# CncBooster_1_1.net
KiCad netlist of a schematic drawn in EAGLE
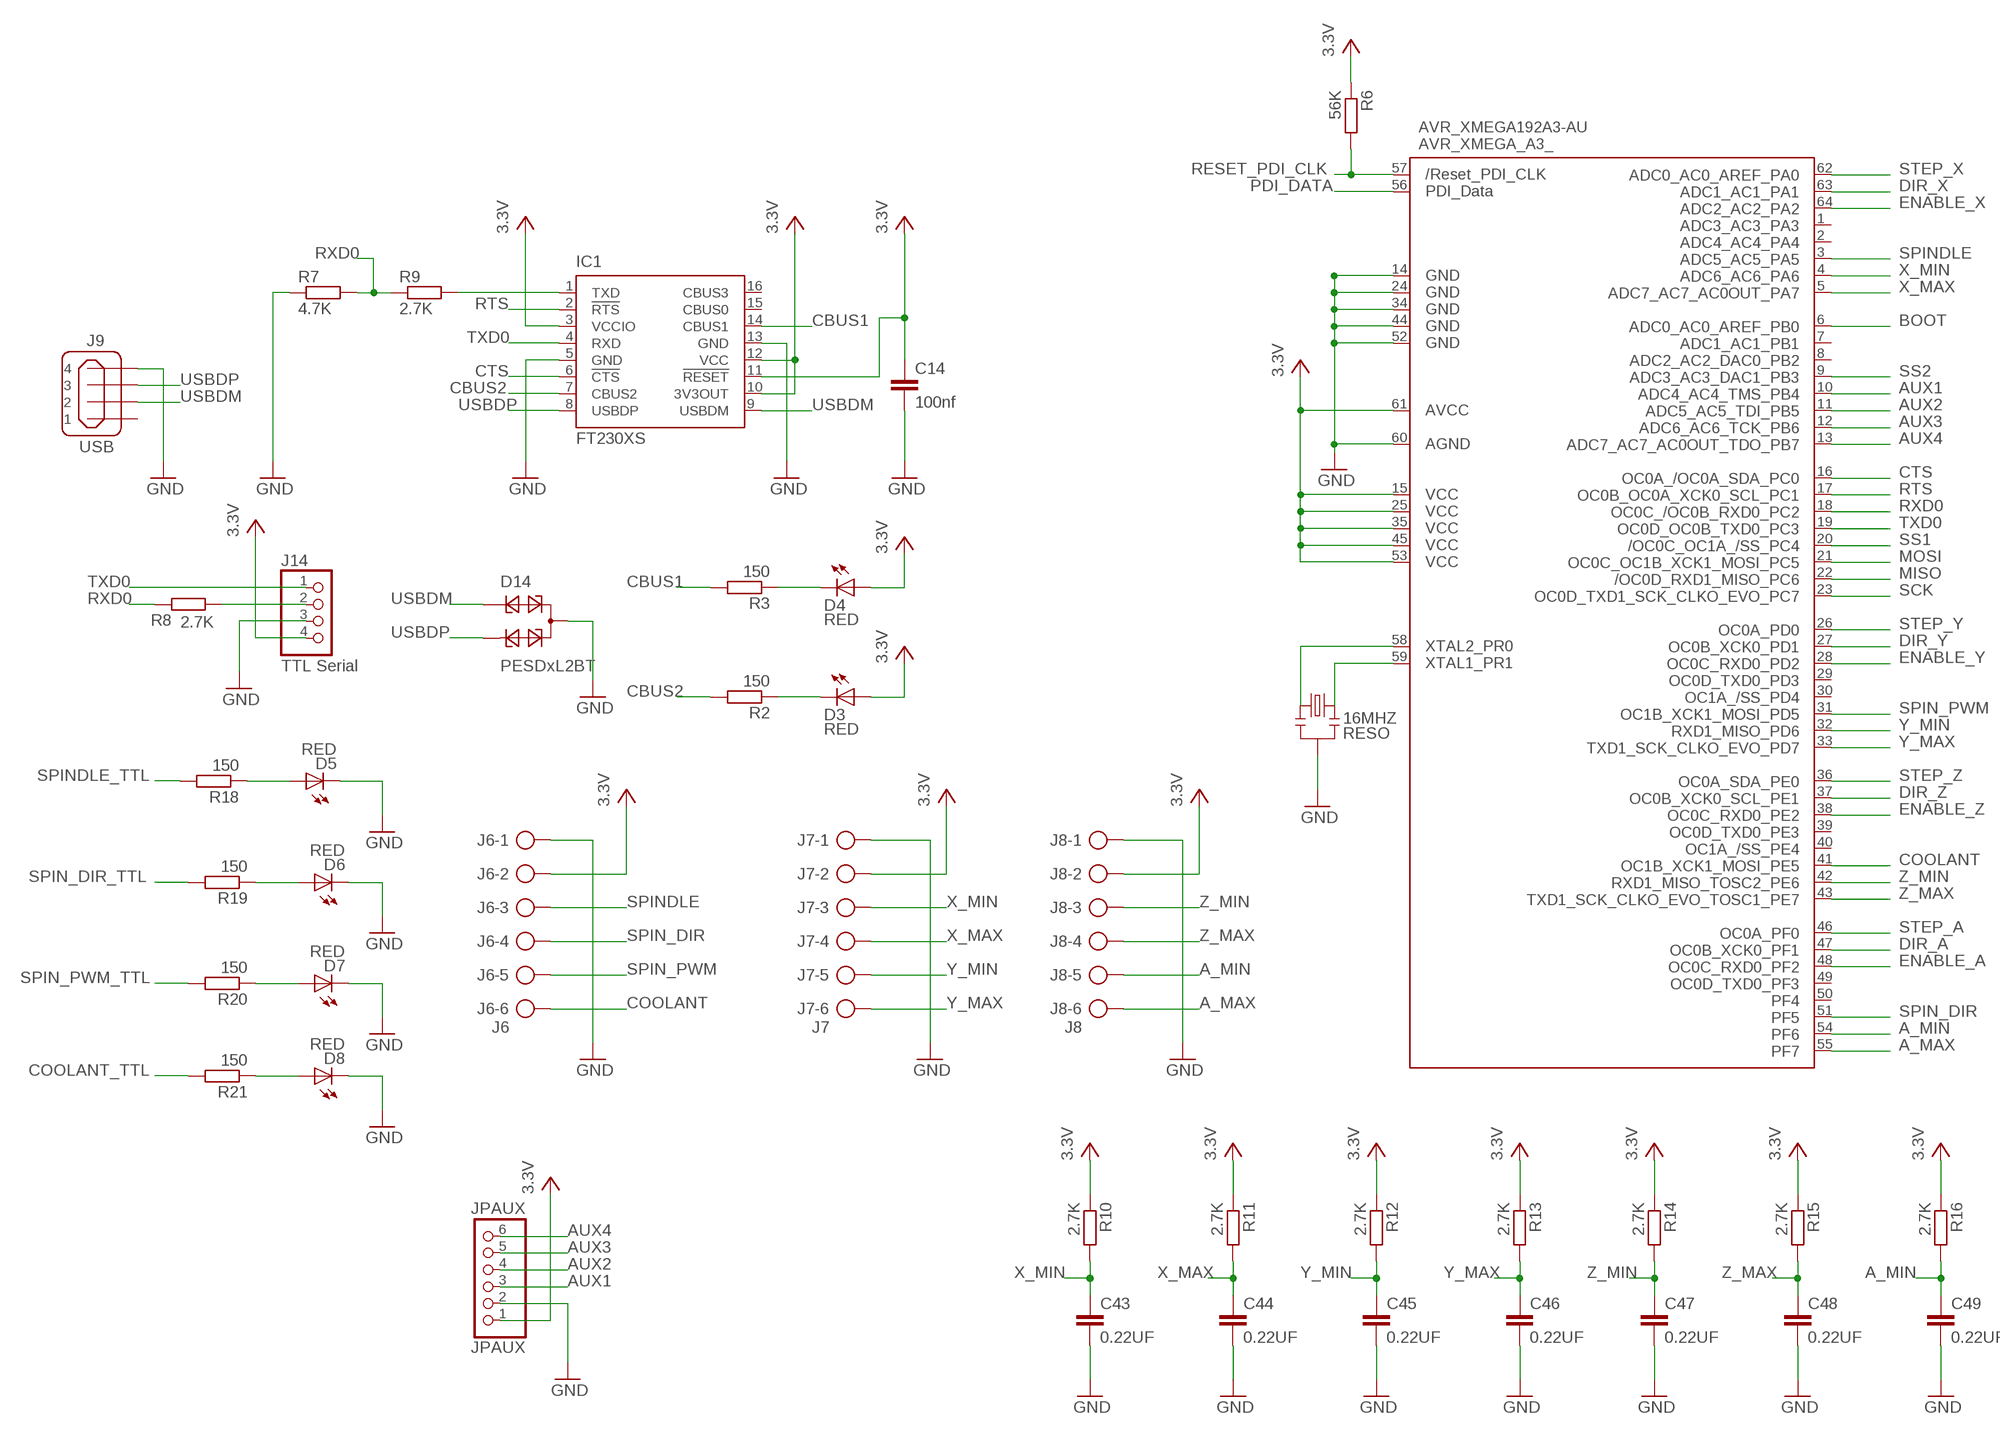
[diagram p0: schematic, sheet 1, part 1 of 2]
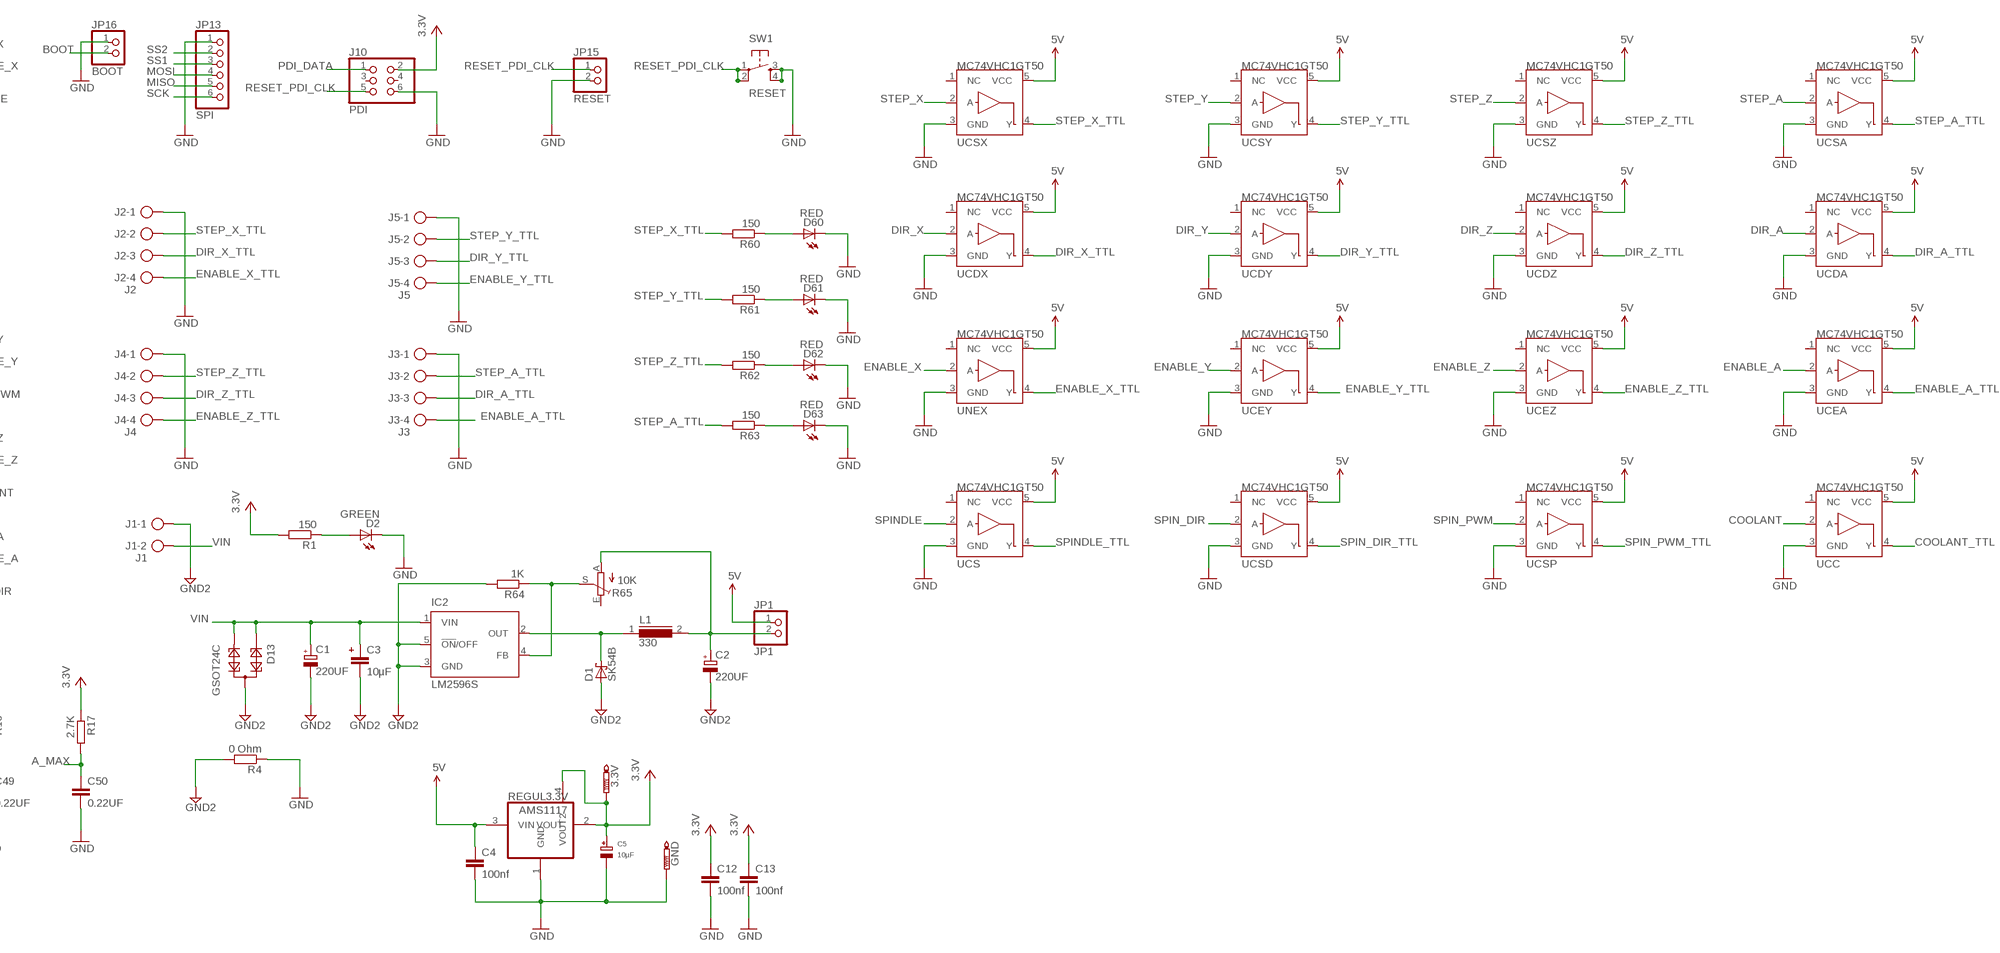
[diagram p1: schematic, sheet 1, part 2 of 2]

(export (version "E")
  (design (tool "Eeschema 10.0.6"))
  (components
    (comp (ref "3.3V")
      (value "PTR1B1,27")
      (footprint "eagle-import:B1,27")
      (libsource (lib "eagle-import") (part "PTR1B1,27"))
    )
    (comp (ref "16MHZ")
      (value "RESO")
      (footprint "eagle-import:RESONATOR_CMS_AWSCR")
      (libsource (lib "eagle-import") (part "RESONATOR_CMS"))
    )
    (comp (ref "AVR_XMEGA192A3-AU")
      (value "AVR_XMEGA_A3_")
      (footprint "eagle-import:TQFP64")
      (libsource (lib "eagle-import") (part "AVR_XMEGA_A3_"))
    )
    (comp (ref "C1")
      (value "220UF")
      (footprint "eagle-import:PANASONIC_E")
      (libsource (lib "eagle-import") (part "CPOL-EUE"))
    )
    (comp (ref "C2")
      (value "220UF")
      (footprint "eagle-import:PANASONIC_E")
      (libsource (lib "eagle-import") (part "CPOL-EUE"))
    )
    (comp (ref "C3")
      (value "10µF")
      (footprint "eagle-import:CONDO_1206")
      (libsource (lib "eagle-import") (part "CONDO_1206_POLA"))
    )
    (comp (ref "C4")
      (value "100nf")
      (footprint "eagle-import:C1206")
      (libsource (lib "eagle-import") (part "C-EUC1206"))
    )
    (comp (ref "C5")
      (value "10µF")
      (footprint "eagle-import:EIA3216-18_A-W")
      (libsource (lib "eagle-import") (part "CAP_TANTALUMA/3216_WAVE"))
    )
    (comp (ref "C12")
      (value "100nf")
      (footprint "eagle-import:C1206")
      (libsource (lib "eagle-import") (part "C-EUC1206"))
    )
    (comp (ref "C13")
      (value "100nf")
      (footprint "eagle-import:C1206")
      (libsource (lib "eagle-import") (part "C-EUC1206"))
    )
    (comp (ref "C14")
      (value "100nf")
      (footprint "eagle-import:C1206")
      (libsource (lib "eagle-import") (part "C-EUC1206"))
    )
    (comp (ref "C43")
      (value "0.22UF")
      (footprint "eagle-import:C1206")
      (libsource (lib "eagle-import") (part "C-EUC1206"))
    )
    (comp (ref "C44")
      (value "0.22UF")
      (footprint "eagle-import:C1206")
      (libsource (lib "eagle-import") (part "C-EUC1206"))
    )
    (comp (ref "C45")
      (value "0.22UF")
      (footprint "eagle-import:C1206")
      (libsource (lib "eagle-import") (part "C-EUC1206"))
    )
    (comp (ref "C46")
      (value "0.22UF")
      (footprint "eagle-import:C1206")
      (libsource (lib "eagle-import") (part "C-EUC1206"))
    )
    (comp (ref "C47")
      (value "0.22UF")
      (footprint "eagle-import:C1206")
      (libsource (lib "eagle-import") (part "C-EUC1206"))
    )
    (comp (ref "C48")
      (value "0.22UF")
      (footprint "eagle-import:C1206")
      (libsource (lib "eagle-import") (part "C-EUC1206"))
    )
    (comp (ref "C49")
      (value "0.22UF")
      (footprint "eagle-import:C1206")
      (libsource (lib "eagle-import") (part "C-EUC1206"))
    )
    (comp (ref "C50")
      (value "0.22UF")
      (footprint "eagle-import:C1206")
      (libsource (lib "eagle-import") (part "C-EUC1206"))
    )
    (comp (ref "D1")
      (value "SK54B")
      (footprint "eagle-import:DO-214AA")
      (libsource (lib "eagle-import") (part "SK54B"))
    )
    (comp (ref "D2")
      (value "GREEN")
      (footprint "eagle-import:CHIPLED_1206")
      (libsource (lib "eagle-import") (part "LEDCHIPLED_1206"))
    )
    (comp (ref "D3")
      (value "RED")
      (footprint "eagle-import:CHIPLED_1206")
      (libsource (lib "eagle-import") (part "LEDCHIPLED_1206"))
    )
    (comp (ref "D4")
      (value "RED")
      (footprint "eagle-import:CHIPLED_1206")
      (libsource (lib "eagle-import") (part "LEDCHIPLED_1206"))
    )
    (comp (ref "D5")
      (value "RED")
      (footprint "eagle-import:CHIPLED_1206")
      (libsource (lib "eagle-import") (part "LEDCHIPLED_1206"))
    )
    (comp (ref "D6")
      (value "RED")
      (footprint "eagle-import:CHIPLED_1206")
      (libsource (lib "eagle-import") (part "LEDCHIPLED_1206"))
    )
    (comp (ref "D7")
      (value "RED")
      (footprint "eagle-import:CHIPLED_1206")
      (libsource (lib "eagle-import") (part "LEDCHIPLED_1206"))
    )
    (comp (ref "D8")
      (value "RED")
      (footprint "eagle-import:CHIPLED_1206")
      (libsource (lib "eagle-import") (part "LEDCHIPLED_1206"))
    )
    (comp (ref "D13")
      (value "GSOT24C")
      (footprint "eagle-import:SOT23")
      (libsource (lib "eagle-import") (part "PESD1CAN"))
    )
    (comp (ref "D14")
      (value "PESDxL2BT")
      (footprint "eagle-import:SOT23")
      (libsource (lib "eagle-import") (part "PESD1CAN"))
    )
    (comp (ref "D60")
      (value "RED")
      (footprint "eagle-import:CHIPLED_1206")
      (libsource (lib "eagle-import") (part "LEDCHIPLED_1206"))
    )
    (comp (ref "D61")
      (value "RED")
      (footprint "eagle-import:CHIPLED_1206")
      (libsource (lib "eagle-import") (part "LEDCHIPLED_1206"))
    )
    (comp (ref "D62")
      (value "RED")
      (footprint "eagle-import:CHIPLED_1206")
      (libsource (lib "eagle-import") (part "LEDCHIPLED_1206"))
    )
    (comp (ref "D63")
      (value "RED")
      (footprint "eagle-import:CHIPLED_1206")
      (libsource (lib "eagle-import") (part "LEDCHIPLED_1206"))
    )
    (comp (ref "GND")
      (value "PTR1B1,27")
      (footprint "eagle-import:B1,27")
      (libsource (lib "eagle-import") (part "PTR1B1,27"))
    )
    (comp (ref "IC1")
      (value "FT230XS")
      (footprint "eagle-import:SSOP16")
      (libsource (lib "eagle-import") (part "FT230XS"))
    )
    (comp (ref "IC2")
      (value "LM2596S")
      (footprint "eagle-import:TO263-5")
      (fields (field (name "MF") "NATIONAL SEMICONDUCTOR") (field (name "MPN") "LM2596S-ADJ/NOPB"))
      (libsource (lib "eagle-import") (part "LM2596S"))
    )
    (comp (ref "J1")
      (value "J1")
      (footprint "eagle-import:AK500_2")
      (libsource (lib "eagle-import") (part "AK500/2"))
    )
    (comp (ref "J2")
      (value "J2")
      (footprint "eagle-import:AK500_4")
      (libsource (lib "eagle-import") (part "AK500/4"))
    )
    (comp (ref "J3")
      (value "J3")
      (footprint "eagle-import:AK500_4")
      (libsource (lib "eagle-import") (part "AK500/4"))
    )
    (comp (ref "J4")
      (value "J4")
      (footprint "eagle-import:AK500_4")
      (libsource (lib "eagle-import") (part "AK500/4"))
    )
    (comp (ref "J5")
      (value "J5")
      (footprint "eagle-import:AK500_4")
      (libsource (lib "eagle-import") (part "AK500/4"))
    )
    (comp (ref "J6")
      (value "J6")
      (footprint "eagle-import:AK500_6")
      (libsource (lib "eagle-import") (part "AK500/6"))
    )
    (comp (ref "J7")
      (value "J7")
      (footprint "eagle-import:AK500_6")
      (libsource (lib "eagle-import") (part "AK500/6"))
    )
    (comp (ref "J8")
      (value "J8")
      (footprint "eagle-import:AK500_6")
      (libsource (lib "eagle-import") (part "AK500/6"))
    )
    (comp (ref "J9")
      (value "USB")
      (footprint "eagle-import:85-32004-10X")
      (libsource (lib "eagle-import") (part "MINI-USB_4P-85-32004-10X"))
    )
    (comp (ref "J10")
      (value "PDI")
      (footprint "eagle-import:2X03")
      (libsource (lib "eagle-import") (part "PINHD-2X3"))
    )
    (comp (ref "J14")
      (value "TTL Serial")
      (footprint "eagle-import:1X04")
      (libsource (lib "eagle-import") (part "PINHD-1X4"))
    )
    (comp (ref "JP1")
      (value "JP1")
      (footprint "eagle-import:1X02")
      (libsource (lib "eagle-import") (part "PINHD-1X2"))
    )
    (comp (ref "JP13")
      (value "SPI")
      (footprint "eagle-import:1X06")
      (libsource (lib "eagle-import") (part "PINHD-1X6"))
    )
    (comp (ref "JP15")
      (value "RESET")
      (footprint "eagle-import:1X02")
      (libsource (lib "eagle-import") (part "PINHD-1X2"))
    )
    (comp (ref "JP16")
      (value "BOOT")
      (footprint "eagle-import:1X02")
      (libsource (lib "eagle-import") (part "PINHD-1X2"))
    )
    (comp (ref "JPAUX")
      (value "JPAUX")
      (footprint "eagle-import:1X06")
      (libsource (lib "eagle-import") (part "PINHD-1X6"))
    )
    (comp (ref "L1")
      (value "330")
      (footprint "eagle-import:DR127")
      (libsource (lib "eagle-import") (part "DR127"))
    )
    (comp (ref "R1")
      (value "150")
      (footprint "eagle-import:R1206")
      (libsource (lib "eagle-import") (part "R-EU_R1206"))
    )
    (comp (ref "R2")
      (value "150")
      (footprint "eagle-import:R1206")
      (libsource (lib "eagle-import") (part "R-EU_R1206"))
    )
    (comp (ref "R3")
      (value "150")
      (footprint "eagle-import:R1206")
      (libsource (lib "eagle-import") (part "R-EU_R1206"))
    )
    (comp (ref "R4")
      (value "0 Ohm")
      (footprint "eagle-import:R1206")
      (libsource (lib "eagle-import") (part "R-EU_R1206"))
    )
    (comp (ref "R6")
      (value "56K")
      (footprint "eagle-import:R1206")
      (libsource (lib "eagle-import") (part "R-EU_R1206"))
    )
    (comp (ref "R7")
      (value "4.7K")
      (footprint "eagle-import:R1206")
      (libsource (lib "eagle-import") (part "R-EU_R1206"))
    )
    (comp (ref "R8")
      (value "2.7K")
      (footprint "eagle-import:R1206")
      (libsource (lib "eagle-import") (part "R-EU_R1206"))
    )
    (comp (ref "R9")
      (value "2.7K")
      (footprint "eagle-import:R1206")
      (libsource (lib "eagle-import") (part "R-EU_R1206"))
    )
    (comp (ref "R10")
      (value "2.7K")
      (footprint "eagle-import:R1206")
      (libsource (lib "eagle-import") (part "R-EU_R1206"))
    )
    (comp (ref "R11")
      (value "2.7K")
      (footprint "eagle-import:R1206")
      (libsource (lib "eagle-import") (part "R-EU_R1206"))
    )
    (comp (ref "R12")
      (value "2.7K")
      (footprint "eagle-import:R1206")
      (libsource (lib "eagle-import") (part "R-EU_R1206"))
    )
    (comp (ref "R13")
      (value "2.7K")
      (footprint "eagle-import:R1206")
      (libsource (lib "eagle-import") (part "R-EU_R1206"))
    )
    (comp (ref "R14")
      (value "2.7K")
      (footprint "eagle-import:R1206")
      (libsource (lib "eagle-import") (part "R-EU_R1206"))
    )
    (comp (ref "R15")
      (value "2.7K")
      (footprint "eagle-import:R1206")
      (libsource (lib "eagle-import") (part "R-EU_R1206"))
    )
    (comp (ref "R16")
      (value "2.7K")
      (footprint "eagle-import:R1206")
      (libsource (lib "eagle-import") (part "R-EU_R1206"))
    )
    (comp (ref "R17")
      (value "2.7K")
      (footprint "eagle-import:R1206")
      (libsource (lib "eagle-import") (part "R-EU_R1206"))
    )
    (comp (ref "R18")
      (value "150")
      (footprint "eagle-import:R1206")
      (libsource (lib "eagle-import") (part "R-EU_R1206"))
    )
    (comp (ref "R19")
      (value "150")
      (footprint "eagle-import:R1206")
      (libsource (lib "eagle-import") (part "R-EU_R1206"))
    )
    (comp (ref "R20")
      (value "150")
      (footprint "eagle-import:R1206")
      (libsource (lib "eagle-import") (part "R-EU_R1206"))
    )
    (comp (ref "R21")
      (value "150")
      (footprint "eagle-import:R1206")
      (libsource (lib "eagle-import") (part "R-EU_R1206"))
    )
    (comp (ref "R60")
      (value "150")
      (footprint "eagle-import:R1206")
      (libsource (lib "eagle-import") (part "R-EU_R1206"))
    )
    (comp (ref "R61")
      (value "150")
      (footprint "eagle-import:R1206")
      (libsource (lib "eagle-import") (part "R-EU_R1206"))
    )
    (comp (ref "R62")
      (value "150")
      (footprint "eagle-import:R1206")
      (libsource (lib "eagle-import") (part "R-EU_R1206"))
    )
    (comp (ref "R63")
      (value "150")
      (footprint "eagle-import:R1206")
      (libsource (lib "eagle-import") (part "R-EU_R1206"))
    )
    (comp (ref "R64")
      (value "1K")
      (footprint "eagle-import:R1206")
      (libsource (lib "eagle-import") (part "R-EU_R1206"))
    )
    (comp (ref "R65")
      (value "10K")
      (footprint "eagle-import:S64W")
      (libsource (lib "eagle-import") (part "TRIM_EU-S64W"))
    )
    (comp (ref "REGUL3.3V")
      (value "AMS1117")
      (footprint "eagle-import:SOT223-A")
      (libsource (lib "eagle-import") (part "AMS1117"))
    )
    (comp (ref "SW1")
      (value "RESET")
      (footprint "eagle-import:TACTILE_SWITCH_SMD")
      (libsource (lib "eagle-import") (part "TAC_SWITCHSMD"))
    )
    (comp (ref "UCC")
      (value "MC74VHC1GT50")
      (footprint "eagle-import:SOT23-5")
      (libsource (lib "eagle-import") (part "MC74VHC1GT50"))
    )
    (comp (ref "UCDA")
      (value "MC74VHC1GT50")
      (footprint "eagle-import:SOT23-5")
      (libsource (lib "eagle-import") (part "MC74VHC1GT50"))
    )
    (comp (ref "UCDX")
      (value "MC74VHC1GT50")
      (footprint "eagle-import:SOT23-5")
      (libsource (lib "eagle-import") (part "MC74VHC1GT50"))
    )
    (comp (ref "UCDY")
      (value "MC74VHC1GT50")
      (footprint "eagle-import:SOT23-5")
      (libsource (lib "eagle-import") (part "MC74VHC1GT50"))
    )
    (comp (ref "UCDZ")
      (value "MC74VHC1GT50")
      (footprint "eagle-import:SOT23-5")
      (libsource (lib "eagle-import") (part "MC74VHC1GT50"))
    )
    (comp (ref "UCEA")
      (value "MC74VHC1GT50")
      (footprint "eagle-import:SOT23-5")
      (libsource (lib "eagle-import") (part "MC74VHC1GT50"))
    )
    (comp (ref "UCEY")
      (value "MC74VHC1GT50")
      (footprint "eagle-import:SOT23-5")
      (libsource (lib "eagle-import") (part "MC74VHC1GT50"))
    )
    (comp (ref "UCEZ")
      (value "MC74VHC1GT50")
      (footprint "eagle-import:SOT23-5")
      (libsource (lib "eagle-import") (part "MC74VHC1GT50"))
    )
    (comp (ref "UCS")
      (value "MC74VHC1GT50")
      (footprint "eagle-import:SOT23-5")
      (libsource (lib "eagle-import") (part "MC74VHC1GT50"))
    )
    (comp (ref "UCSA")
      (value "MC74VHC1GT50")
      (footprint "eagle-import:SOT23-5")
      (libsource (lib "eagle-import") (part "MC74VHC1GT50"))
    )
    (comp (ref "UCSD")
      (value "MC74VHC1GT50")
      (footprint "eagle-import:SOT23-5")
      (libsource (lib "eagle-import") (part "MC74VHC1GT50"))
    )
    (comp (ref "UCSP")
      (value "MC74VHC1GT50")
      (footprint "eagle-import:SOT23-5")
      (libsource (lib "eagle-import") (part "MC74VHC1GT50"))
    )
    (comp (ref "UCSX")
      (value "MC74VHC1GT50")
      (footprint "eagle-import:SOT23-5")
      (libsource (lib "eagle-import") (part "MC74VHC1GT50"))
    )
    (comp (ref "UCSY")
      (value "MC74VHC1GT50")
      (footprint "eagle-import:SOT23-5")
      (libsource (lib "eagle-import") (part "MC74VHC1GT50"))
    )
    (comp (ref "UCSZ")
      (value "MC74VHC1GT50")
      (footprint "eagle-import:SOT23-5")
      (libsource (lib "eagle-import") (part "MC74VHC1GT50"))
    )
    (comp (ref "UNEX")
      (value "MC74VHC1GT50")
      (footprint "eagle-import:SOT23-5")
      (libsource (lib "eagle-import") (part "MC74VHC1GT50"))
    )
  )
  (nets
    (net (code "1") (name "/AUX1") (class "Default")
      (node (ref "AVR_XMEGA192A3-AU") (pin "10") (pinfunction "PB4_10") (pintype "bidirectional"))
      (node (ref "JPAUX") (pin "3") (pinfunction "3_3") (pintype "passive"))
    )
    (net (code "2") (name "/AUX2") (class "Default")
      (node (ref "AVR_XMEGA192A3-AU") (pin "11") (pinfunction "PB5_11") (pintype "bidirectional"))
      (node (ref "JPAUX") (pin "4") (pinfunction "4_4") (pintype "passive"))
    )
    (net (code "3") (name "/AUX3") (class "Default")
      (node (ref "AVR_XMEGA192A3-AU") (pin "12") (pinfunction "PB6_12") (pintype "bidirectional"))
      (node (ref "JPAUX") (pin "5") (pinfunction "5_5") (pintype "passive"))
    )
    (net (code "4") (name "/AUX4") (class "Default")
      (node (ref "AVR_XMEGA192A3-AU") (pin "13") (pinfunction "PB7_13") (pintype "bidirectional"))
      (node (ref "JPAUX") (pin "6") (pinfunction "6_6") (pintype "passive"))
    )
    (net (code "5") (name "/A_MAX") (class "Default")
      (node (ref "AVR_XMEGA192A3-AU") (pin "55") (pinfunction "PF7_55") (pintype "bidirectional"))
      (node (ref "C50") (pin "1") (pinfunction "1_1") (pintype "passive"))
      (node (ref "J8") (pin "6") (pinfunction "KL_6") (pintype "passive"))
      (node (ref "R17") (pin "2") (pinfunction "2_2") (pintype "passive"))
    )
    (net (code "6") (name "/A_MIN") (class "Default")
      (node (ref "AVR_XMEGA192A3-AU") (pin "54") (pinfunction "PF6_54") (pintype "bidirectional"))
      (node (ref "C49") (pin "1") (pinfunction "1_1") (pintype "passive"))
      (node (ref "J8") (pin "5") (pinfunction "KL_5") (pintype "passive"))
      (node (ref "R16") (pin "2") (pinfunction "2_2") (pintype "passive"))
    )
    (net (code "7") (name "/BOOT") (class "Default")
      (node (ref "AVR_XMEGA192A3-AU") (pin "6") (pinfunction "PB0_6") (pintype "bidirectional"))
      (node (ref "JP16") (pin "2") (pinfunction "2_2") (pintype "passive"))
    )
    (net (code "8") (name "/CBUS1") (class "Default")
      (node (ref "IC1") (pin "14") (pinfunction "CBUS1_14") (pintype "bidirectional"))
      (node (ref "R3") (pin "2") (pinfunction "2_2") (pintype "passive"))
    )
    (net (code "9") (name "/CBUS2") (class "Default")
      (node (ref "IC1") (pin "7") (pinfunction "CBUS2_7") (pintype "bidirectional"))
      (node (ref "R2") (pin "2") (pinfunction "2_2") (pintype "passive"))
    )
    (net (code "10") (name "/COOLANT") (class "Default")
      (node (ref "AVR_XMEGA192A3-AU") (pin "41") (pinfunction "PE5_41") (pintype "bidirectional"))
      (node (ref "J6") (pin "6") (pinfunction "KL_6") (pintype "passive"))
      (node (ref "UCC") (pin "2") (pinfunction "A_2") (pintype "bidirectional"))
    )
    (net (code "11") (name "/COOLANT_TTL") (class "Default")
      (node (ref "R21") (pin "2") (pinfunction "2_2") (pintype "passive"))
      (node (ref "UCC") (pin "4") (pinfunction "Y_4") (pintype "bidirectional"))
    )
    (net (code "12") (name "/CTS") (class "Default")
      (node (ref "AVR_XMEGA192A3-AU") (pin "16") (pinfunction "PC0_16") (pintype "bidirectional"))
      (node (ref "IC1") (pin "6") (pinfunction "~{CTS}_6") (pintype "input"))
    )
    (net (code "13") (name "/DIR_A") (class "Default")
      (node (ref "AVR_XMEGA192A3-AU") (pin "47") (pinfunction "PF1_47") (pintype "bidirectional"))
      (node (ref "UCDA") (pin "2") (pinfunction "A_2") (pintype "bidirectional"))
    )
    (net (code "14") (name "/DIR_A_TTL") (class "Default")
      (node (ref "J3") (pin "3") (pinfunction "KL_3") (pintype "passive"))
      (node (ref "UCDA") (pin "4") (pinfunction "Y_4") (pintype "bidirectional"))
    )
    (net (code "15") (name "/DIR_X") (class "Default")
      (node (ref "AVR_XMEGA192A3-AU") (pin "63") (pinfunction "PA1_63") (pintype "bidirectional"))
      (node (ref "UCDX") (pin "2") (pinfunction "A_2") (pintype "bidirectional"))
    )
    (net (code "16") (name "/DIR_X_TTL") (class "Default")
      (node (ref "J2") (pin "3") (pinfunction "KL_3") (pintype "passive"))
      (node (ref "UCDX") (pin "4") (pinfunction "Y_4") (pintype "bidirectional"))
    )
    (net (code "17") (name "/DIR_Y") (class "Default")
      (node (ref "AVR_XMEGA192A3-AU") (pin "27") (pinfunction "PD1_27") (pintype "bidirectional"))
      (node (ref "UCDY") (pin "2") (pinfunction "A_2") (pintype "bidirectional"))
    )
    (net (code "18") (name "/DIR_Y_TTL") (class "Default")
      (node (ref "J5") (pin "3") (pinfunction "KL_3") (pintype "passive"))
      (node (ref "UCDY") (pin "4") (pinfunction "Y_4") (pintype "bidirectional"))
    )
    (net (code "19") (name "/DIR_Z") (class "Default")
      (node (ref "AVR_XMEGA192A3-AU") (pin "37") (pinfunction "PE1_37") (pintype "bidirectional"))
      (node (ref "UCDZ") (pin "2") (pinfunction "A_2") (pintype "bidirectional"))
    )
    (net (code "20") (name "/DIR_Z_TTL") (class "Default")
      (node (ref "J4") (pin "3") (pinfunction "KL_3") (pintype "passive"))
      (node (ref "UCDZ") (pin "4") (pinfunction "Y_4") (pintype "bidirectional"))
    )
    (net (code "21") (name "/ENABLE_A") (class "Default")
      (node (ref "AVR_XMEGA192A3-AU") (pin "48") (pinfunction "PF2_48") (pintype "bidirectional"))
      (node (ref "UCEA") (pin "2") (pinfunction "A_2") (pintype "bidirectional"))
    )
    (net (code "22") (name "/ENABLE_A_TTL") (class "Default")
      (node (ref "J3") (pin "4") (pinfunction "KL_4") (pintype "passive"))
      (node (ref "UCEA") (pin "4") (pinfunction "Y_4") (pintype "bidirectional"))
    )
    (net (code "23") (name "/ENABLE_X") (class "Default")
      (node (ref "AVR_XMEGA192A3-AU") (pin "64") (pinfunction "PA2_64") (pintype "bidirectional"))
      (node (ref "UNEX") (pin "2") (pinfunction "A_2") (pintype "bidirectional"))
    )
    (net (code "24") (name "/ENABLE_X_TTL") (class "Default")
      (node (ref "J2") (pin "4") (pinfunction "KL_4") (pintype "passive"))
      (node (ref "UNEX") (pin "4") (pinfunction "Y_4") (pintype "bidirectional"))
    )
    (net (code "25") (name "/ENABLE_Y") (class "Default")
      (node (ref "AVR_XMEGA192A3-AU") (pin "28") (pinfunction "PD2_28") (pintype "bidirectional"))
      (node (ref "UCEY") (pin "2") (pinfunction "A_2") (pintype "bidirectional"))
    )
    (net (code "26") (name "/ENABLE_Y_TTL") (class "Default")
      (node (ref "J5") (pin "4") (pinfunction "KL_4") (pintype "passive"))
      (node (ref "UCEY") (pin "4") (pinfunction "Y_4") (pintype "bidirectional"))
    )
    (net (code "27") (name "/ENABLE_Z") (class "Default")
      (node (ref "AVR_XMEGA192A3-AU") (pin "38") (pinfunction "PE2_38") (pintype "bidirectional"))
      (node (ref "UCEZ") (pin "2") (pinfunction "A_2") (pintype "bidirectional"))
    )
    (net (code "28") (name "/ENABLE_Z_TTL") (class "Default")
      (node (ref "J4") (pin "4") (pinfunction "KL_4") (pintype "passive"))
      (node (ref "UCEZ") (pin "4") (pinfunction "Y_4") (pintype "bidirectional"))
    )
    (net (code "29") (name "/MISO") (class "Default")
      (node (ref "AVR_XMEGA192A3-AU") (pin "22") (pinfunction "PC6_22") (pintype "bidirectional"))
      (node (ref "JP13") (pin "5") (pinfunction "5_5") (pintype "passive"))
    )
    (net (code "30") (name "/MOSI") (class "Default")
      (node (ref "AVR_XMEGA192A3-AU") (pin "21") (pinfunction "PC5_21") (pintype "bidirectional"))
      (node (ref "JP13") (pin "4") (pinfunction "4_4") (pintype "passive"))
    )
    (net (code "31") (name "/PDI_DATA") (class "Default")
      (node (ref "AVR_XMEGA192A3-AU") (pin "56") (pinfunction "PDI_DATA_56") (pintype "bidirectional"))
      (node (ref "J10") (pin "1") (pinfunction "1_1") (pintype "passive"))
    )
    (net (code "32") (name "/RESET_PDI_CLK") (class "Default")
      (node (ref "AVR_XMEGA192A3-AU") (pin "57") (pinfunction "RESET_57") (pintype "bidirectional"))
      (node (ref "J10") (pin "5") (pinfunction "5_5") (pintype "passive"))
      (node (ref "JP15") (pin "1") (pinfunction "1_1") (pintype "passive"))
      (node (ref "R6") (pin "2") (pinfunction "2_2") (pintype "passive"))
      (node (ref "SW1") (pin "1") (pinfunction "1_1") (pintype "passive"))
      (node (ref "SW1") (pin "2") (pinfunction "2_2") (pintype "passive"))
    )
    (net (code "33") (name "/RTS") (class "Default")
      (node (ref "AVR_XMEGA192A3-AU") (pin "17") (pinfunction "PC1_17") (pintype "bidirectional"))
      (node (ref "IC1") (pin "2") (pinfunction "~{RTS}_2") (pintype "output"))
    )
    (net (code "34") (name "/RXD0") (class "Default")
      (node (ref "AVR_XMEGA192A3-AU") (pin "18") (pinfunction "PC2_18") (pintype "bidirectional"))
      (node (ref "R7") (pin "2") (pinfunction "2_2") (pintype "passive"))
      (node (ref "R8") (pin "2") (pinfunction "2_2") (pintype "passive"))
      (node (ref "R9") (pin "1") (pinfunction "1_1") (pintype "passive"))
    )
    (net (code "35") (name "/SCK") (class "Default")
      (node (ref "AVR_XMEGA192A3-AU") (pin "23") (pinfunction "PC7_23") (pintype "bidirectional"))
      (node (ref "JP13") (pin "6") (pinfunction "6_6") (pintype "passive"))
    )
    (net (code "36") (name "/SPINDLE") (class "Default")
      (node (ref "AVR_XMEGA192A3-AU") (pin "3") (pinfunction "PA5_3") (pintype "bidirectional"))
      (node (ref "J6") (pin "3") (pinfunction "KL_3") (pintype "passive"))
      (node (ref "UCS") (pin "2") (pinfunction "A_2") (pintype "bidirectional"))
    )
    (net (code "37") (name "/SPINDLE_TTL") (class "Default")
      (node (ref "R18") (pin "2") (pinfunction "2_2") (pintype "passive"))
      (node (ref "UCS") (pin "4") (pinfunction "Y_4") (pintype "bidirectional"))
    )
    (net (code "38") (name "/SPIN_DIR") (class "Default")
      (node (ref "AVR_XMEGA192A3-AU") (pin "51") (pinfunction "PF5_51") (pintype "bidirectional"))
      (node (ref "J6") (pin "4") (pinfunction "KL_4") (pintype "passive"))
      (node (ref "UCSD") (pin "2") (pinfunction "A_2") (pintype "bidirectional"))
    )
    (net (code "39") (name "/SPIN_DIR_TTL") (class "Default")
      (node (ref "R19") (pin "2") (pinfunction "2_2") (pintype "passive"))
      (node (ref "UCSD") (pin "4") (pinfunction "Y_4") (pintype "bidirectional"))
    )
    (net (code "40") (name "/SPIN_PWM") (class "Default")
      (node (ref "AVR_XMEGA192A3-AU") (pin "31") (pinfunction "PD5_31") (pintype "bidirectional"))
      (node (ref "J6") (pin "5") (pinfunction "KL_5") (pintype "passive"))
      (node (ref "UCSP") (pin "2") (pinfunction "A_2") (pintype "bidirectional"))
    )
    (net (code "41") (name "/SPIN_PWM_TTL") (class "Default")
      (node (ref "R20") (pin "2") (pinfunction "2_2") (pintype "passive"))
      (node (ref "UCSP") (pin "4") (pinfunction "Y_4") (pintype "bidirectional"))
    )
    (net (code "42") (name "/SS1") (class "Default")
      (node (ref "AVR_XMEGA192A3-AU") (pin "20") (pinfunction "PC4_20") (pintype "bidirectional"))
      (node (ref "JP13") (pin "3") (pinfunction "3_3") (pintype "passive"))
    )
    (net (code "43") (name "/SS2") (class "Default")
      (node (ref "AVR_XMEGA192A3-AU") (pin "9") (pinfunction "PB3_9") (pintype "bidirectional"))
      (node (ref "JP13") (pin "2") (pinfunction "2_2") (pintype "passive"))
    )
    (net (code "44") (name "/STEP_A") (class "Default")
      (node (ref "AVR_XMEGA192A3-AU") (pin "46") (pinfunction "PF0_46") (pintype "bidirectional"))
      (node (ref "UCSA") (pin "2") (pinfunction "A_2") (pintype "bidirectional"))
    )
    (net (code "45") (name "/STEP_A_TTL") (class "Default")
      (node (ref "J3") (pin "2") (pinfunction "KL_2") (pintype "passive"))
      (node (ref "R63") (pin "2") (pinfunction "2_2") (pintype "passive"))
      (node (ref "UCSA") (pin "4") (pinfunction "Y_4") (pintype "bidirectional"))
    )
    (net (code "46") (name "/STEP_X") (class "Default")
      (node (ref "AVR_XMEGA192A3-AU") (pin "62") (pinfunction "PA0_62") (pintype "bidirectional"))
      (node (ref "UCSX") (pin "2") (pinfunction "A_2") (pintype "bidirectional"))
    )
    (net (code "47") (name "/STEP_X_TTL") (class "Default")
      (node (ref "J2") (pin "2") (pinfunction "KL_2") (pintype "passive"))
      (node (ref "R60") (pin "2") (pinfunction "2_2") (pintype "passive"))
      (node (ref "UCSX") (pin "4") (pinfunction "Y_4") (pintype "bidirectional"))
    )
    (net (code "48") (name "/STEP_Y") (class "Default")
      (node (ref "AVR_XMEGA192A3-AU") (pin "26") (pinfunction "PD0_26") (pintype "bidirectional"))
      (node (ref "UCSY") (pin "2") (pinfunction "A_2") (pintype "bidirectional"))
    )
    (net (code "49") (name "/STEP_Y_TTL") (class "Default")
      (node (ref "J5") (pin "2") (pinfunction "KL_2") (pintype "passive"))
      (node (ref "R61") (pin "2") (pinfunction "2_2") (pintype "passive"))
      (node (ref "UCSY") (pin "4") (pinfunction "Y_4") (pintype "bidirectional"))
    )
    (net (code "50") (name "/STEP_Z") (class "Default")
      (node (ref "AVR_XMEGA192A3-AU") (pin "36") (pinfunction "PE0_36") (pintype "bidirectional"))
      (node (ref "UCSZ") (pin "2") (pinfunction "A_2") (pintype "bidirectional"))
    )
    (net (code "51") (name "/STEP_Z_TTL") (class "Default")
      (node (ref "J4") (pin "2") (pinfunction "KL_2") (pintype "passive"))
      (node (ref "R62") (pin "2") (pinfunction "2_2") (pintype "passive"))
      (node (ref "UCSZ") (pin "4") (pinfunction "Y_4") (pintype "bidirectional"))
    )
    (net (code "52") (name "/TXD0") (class "Default")
      (node (ref "AVR_XMEGA192A3-AU") (pin "19") (pinfunction "PC3_19") (pintype "bidirectional"))
      (node (ref "IC1") (pin "4") (pinfunction "RXD_4") (pintype "input"))
      (node (ref "J14") (pin "1") (pinfunction "1_1") (pintype "passive"))
    )
    (net (code "53") (name "/USBDM") (class "Default")
      (node (ref "D14") (pin "1") (pinfunction "1_1") (pintype "passive"))
      (node (ref "IC1") (pin "9") (pinfunction "USBDM_9") (pintype "input"))
      (node (ref "J9") (pin "2") (pinfunction "2_2") (pintype "passive"))
    )
    (net (code "54") (name "/USBDP") (class "Default")
      (node (ref "D14") (pin "2") (pinfunction "2_2") (pintype "passive"))
      (node (ref "IC1") (pin "8") (pinfunction "USBDP_8") (pintype "input"))
      (node (ref "J9") (pin "3") (pinfunction "3_3") (pintype "passive"))
    )
    (net (code "55") (name "/VIN") (class "Default")
      (node (ref "C1") (pin "+") (pinfunction "+_+") (pintype "passive"))
      (node (ref "C3") (pin "2") (pinfunction "1_2") (pintype "passive"))
      (node (ref "D13") (pin "1") (pinfunction "1_1") (pintype "passive"))
      (node (ref "D13") (pin "2") (pinfunction "2_2") (pintype "passive"))
      (node (ref "IC2") (pin "1") (pinfunction "VIN_1") (pintype "input"))
      (node (ref "J1") (pin "2") (pinfunction "KL_2") (pintype "passive"))
    )
    (net (code "56") (name "/X_MAX") (class "Default")
      (node (ref "AVR_XMEGA192A3-AU") (pin "5") (pinfunction "PA7_5") (pintype "bidirectional"))
      (node (ref "C44") (pin "1") (pinfunction "1_1") (pintype "passive"))
      (node (ref "J7") (pin "4") (pinfunction "KL_4") (pintype "passive"))
      (node (ref "R11") (pin "2") (pinfunction "2_2") (pintype "passive"))
    )
    (net (code "57") (name "/X_MIN") (class "Default")
      (node (ref "AVR_XMEGA192A3-AU") (pin "4") (pinfunction "PA6_4") (pintype "bidirectional"))
      (node (ref "C43") (pin "1") (pinfunction "1_1") (pintype "passive"))
      (node (ref "J7") (pin "3") (pinfunction "KL_3") (pintype "passive"))
      (node (ref "R10") (pin "2") (pinfunction "2_2") (pintype "passive"))
    )
    (net (code "58") (name "/Y_MAX") (class "Default")
      (node (ref "AVR_XMEGA192A3-AU") (pin "33") (pinfunction "PD7_33") (pintype "bidirectional"))
      (node (ref "C46") (pin "1") (pinfunction "1_1") (pintype "passive"))
      (node (ref "J7") (pin "6") (pinfunction "KL_6") (pintype "passive"))
      (node (ref "R13") (pin "2") (pinfunction "2_2") (pintype "passive"))
    )
    (net (code "59") (name "/Y_MIN") (class "Default")
      (node (ref "AVR_XMEGA192A3-AU") (pin "32") (pinfunction "PD6_32") (pintype "bidirectional"))
      (node (ref "C45") (pin "1") (pinfunction "1_1") (pintype "passive"))
      (node (ref "J7") (pin "5") (pinfunction "KL_5") (pintype "passive"))
      (node (ref "R12") (pin "2") (pinfunction "2_2") (pintype "passive"))
    )
    (net (code "60") (name "/Z_MAX") (class "Default")
      (node (ref "AVR_XMEGA192A3-AU") (pin "43") (pinfunction "PE7_43") (pintype "bidirectional"))
      (node (ref "C48") (pin "1") (pinfunction "1_1") (pintype "passive"))
      (node (ref "J8") (pin "4") (pinfunction "KL_4") (pintype "passive"))
      (node (ref "R15") (pin "2") (pinfunction "2_2") (pintype "passive"))
    )
    (net (code "61") (name "/Z_MIN") (class "Default")
      (node (ref "AVR_XMEGA192A3-AU") (pin "42") (pinfunction "PE6_42") (pintype "bidirectional"))
      (node (ref "C47") (pin "1") (pinfunction "1_1") (pintype "passive"))
      (node (ref "J8") (pin "3") (pinfunction "KL_3") (pintype "passive"))
      (node (ref "R14") (pin "2") (pinfunction "2_2") (pintype "passive"))
    )
    (net (code "62") (name "3.3V") (class "Default")
      (node (ref "3.3V") (pin "TP") (pinfunction "TP_TP") (pintype "input"))
      (node (ref "AVR_XMEGA192A3-AU") (pin "15") (pinfunction "VCC1_15") (pintype "bidirectional"))
      (node (ref "AVR_XMEGA192A3-AU") (pin "25") (pinfunction "VCC2_25") (pintype "bidirectional"))
      (node (ref "AVR_XMEGA192A3-AU") (pin "35") (pinfunction "VCC3_35") (pintype "bidirectional"))
      (node (ref "AVR_XMEGA192A3-AU") (pin "45") (pinfunction "VCC4_45") (pintype "bidirectional"))
      (node (ref "AVR_XMEGA192A3-AU") (pin "53") (pinfunction "VCC5_53") (pintype "bidirectional"))
      (node (ref "AVR_XMEGA192A3-AU") (pin "61") (pinfunction "AVCC_61") (pintype "bidirectional"))
      (node (ref "C12") (pin "1") (pinfunction "1_1") (pintype "passive"))
      (node (ref "C13") (pin "1") (pinfunction "1_1") (pintype "passive"))
      (node (ref "C14") (pin "1") (pinfunction "1_1") (pintype "passive"))
      (node (ref "C5") (pin "+") (pinfunction "+_+") (pintype "passive"))
      (node (ref "D3") (pin "A") (pinfunction "A_A") (pintype "passive"))
      (node (ref "D4") (pin "A") (pinfunction "A_A") (pintype "passive"))
      (node (ref "IC1") (pin "10") (pinfunction "3V3OUT_10") (pintype "output"))
      (node (ref "IC1") (pin "11") (pinfunction "~{RESET}_11") (pintype "input"))
      (node (ref "IC1") (pin "12") (pinfunction "VCC_12") (pintype "power_in"))
      (node (ref "IC1") (pin "3") (pinfunction "VCCIO_3") (pintype "power_in"))
      (node (ref "J10") (pin "2") (pinfunction "2_2") (pintype "passive"))
      (node (ref "J14") (pin "4") (pinfunction "4_4") (pintype "passive"))
      (node (ref "J6") (pin "2") (pinfunction "KL_2") (pintype "passive"))
      (node (ref "J7") (pin "2") (pinfunction "KL_2") (pintype "passive"))
      (node (ref "J8") (pin "2") (pinfunction "KL_2") (pintype "passive"))
      (node (ref "JPAUX") (pin "1") (pinfunction "1_1") (pintype "passive"))
      (node (ref "R1") (pin "2") (pinfunction "2_2") (pintype "passive"))
      (node (ref "R10") (pin "1") (pinfunction "1_1") (pintype "passive"))
      (node (ref "R11") (pin "1") (pinfunction "1_1") (pintype "passive"))
      (node (ref "R12") (pin "1") (pinfunction "1_1") (pintype "passive"))
      (node (ref "R13") (pin "1") (pinfunction "1_1") (pintype "passive"))
      (node (ref "R14") (pin "1") (pinfunction "1_1") (pintype "passive"))
      (node (ref "R15") (pin "1") (pinfunction "1_1") (pintype "passive"))
      (node (ref "R16") (pin "1") (pinfunction "1_1") (pintype "passive"))
      (node (ref "R17") (pin "1") (pinfunction "1_1") (pintype "passive"))
      (node (ref "R6") (pin "1") (pinfunction "1_1") (pintype "passive"))
      (node (ref "REGUL3.3V") (pin "2") (pinfunction "VOUT_2") (pintype "output"))
      (node (ref "REGUL3.3V") (pin "4") (pinfunction "VOUT2_4") (pintype "output"))
    )
    (net (code "63") (name "5V") (class "Default")
      (node (ref "C4") (pin "1") (pinfunction "1_1") (pintype "passive"))
      (node (ref "JP1") (pin "1") (pinfunction "1_1") (pintype "passive"))
      (node (ref "REGUL3.3V") (pin "3") (pinfunction "VIN_3") (pintype "input"))
      (node (ref "UCC") (pin "5") (pinfunction "VCC_5") (pintype "bidirectional"))
      (node (ref "UCDA") (pin "5") (pinfunction "VCC_5") (pintype "bidirectional"))
      (node (ref "UCDX") (pin "5") (pinfunction "VCC_5") (pintype "bidirectional"))
      (node (ref "UCDY") (pin "5") (pinfunction "VCC_5") (pintype "bidirectional"))
      (node (ref "UCDZ") (pin "5") (pinfunction "VCC_5") (pintype "bidirectional"))
      (node (ref "UCEA") (pin "5") (pinfunction "VCC_5") (pintype "bidirectional"))
      (node (ref "UCEY") (pin "5") (pinfunction "VCC_5") (pintype "bidirectional"))
      (node (ref "UCEZ") (pin "5") (pinfunction "VCC_5") (pintype "bidirectional"))
      (node (ref "UCS") (pin "5") (pinfunction "VCC_5") (pintype "bidirectional"))
      (node (ref "UCSA") (pin "5") (pinfunction "VCC_5") (pintype "bidirectional"))
      (node (ref "UCSD") (pin "5") (pinfunction "VCC_5") (pintype "bidirectional"))
      (node (ref "UCSP") (pin "5") (pinfunction "VCC_5") (pintype "bidirectional"))
      (node (ref "UCSX") (pin "5") (pinfunction "VCC_5") (pintype "bidirectional"))
      (node (ref "UCSY") (pin "5") (pinfunction "VCC_5") (pintype "bidirectional"))
      (node (ref "UCSZ") (pin "5") (pinfunction "VCC_5") (pintype "bidirectional"))
      (node (ref "UNEX") (pin "5") (pinfunction "VCC_5") (pintype "bidirectional"))
    )
    (net (code "64") (name "GND") (class "Default")
      (node (ref "16MHZ") (pin "P$3") (pinfunction "2_P$3") (pintype "passive"))
      (node (ref "AVR_XMEGA192A3-AU") (pin "14") (pinfunction "GND1_14") (pintype "bidirectional"))
      (node (ref "AVR_XMEGA192A3-AU") (pin "24") (pinfunction "GND2_24") (pintype "bidirectional"))
      (node (ref "AVR_XMEGA192A3-AU") (pin "34") (pinfunction "GND3_34") (pintype "bidirectional"))
      (node (ref "AVR_XMEGA192A3-AU") (pin "44") (pinfunction "GND4_44") (pintype "bidirectional"))
      (node (ref "AVR_XMEGA192A3-AU") (pin "52") (pinfunction "GND5_52") (pintype "bidirectional"))
      (node (ref "AVR_XMEGA192A3-AU") (pin "60") (pinfunction "AGND_60") (pintype "bidirectional"))
      (node (ref "C12") (pin "2") (pinfunction "2_2") (pintype "passive"))
      (node (ref "C13") (pin "2") (pinfunction "2_2") (pintype "passive"))
      (node (ref "C14") (pin "2") (pinfunction "2_2") (pintype "passive"))
      (node (ref "C4") (pin "2") (pinfunction "2_2") (pintype "passive"))
      (node (ref "C43") (pin "2") (pinfunction "2_2") (pintype "passive"))
      (node (ref "C44") (pin "2") (pinfunction "2_2") (pintype "passive"))
      (node (ref "C45") (pin "2") (pinfunction "2_2") (pintype "passive"))
      (node (ref "C46") (pin "2") (pinfunction "2_2") (pintype "passive"))
      (node (ref "C47") (pin "2") (pinfunction "2_2") (pintype "passive"))
      (node (ref "C48") (pin "2") (pinfunction "2_2") (pintype "passive"))
      (node (ref "C49") (pin "2") (pinfunction "2_2") (pintype "passive"))
      (node (ref "C5") (pin "-") (pinfunction "-_-") (pintype "passive"))
      (node (ref "C50") (pin "2") (pinfunction "2_2") (pintype "passive"))
      (node (ref "D14") (pin "3") (pinfunction "3_3") (pintype "passive"))
      (node (ref "D2") (pin "C") (pinfunction "C_C") (pintype "passive"))
      (node (ref "D5") (pin "C") (pinfunction "C_C") (pintype "passive"))
      (node (ref "D6") (pin "C") (pinfunction "C_C") (pintype "passive"))
      (node (ref "D60") (pin "C") (pinfunction "C_C") (pintype "passive"))
      (node (ref "D61") (pin "C") (pinfunction "C_C") (pintype "passive"))
      (node (ref "D62") (pin "C") (pinfunction "C_C") (pintype "passive"))
      (node (ref "D63") (pin "C") (pinfunction "C_C") (pintype "passive"))
      (node (ref "D7") (pin "C") (pinfunction "C_C") (pintype "passive"))
      (node (ref "D8") (pin "C") (pinfunction "C_C") (pintype "passive"))
      (node (ref "GND") (pin "TP") (pinfunction "TP_TP") (pintype "input"))
      (node (ref "IC1") (pin "13") (pinfunction "GND_13") (pintype "power_in"))
      (node (ref "IC1") (pin "5") (pinfunction "GND_5") (pintype "power_in"))
      (node (ref "J10") (pin "6") (pinfunction "6_6") (pintype "passive"))
      (node (ref "J14") (pin "3") (pinfunction "3_3") (pintype "passive"))
      (node (ref "J2") (pin "1") (pinfunction "KL_1") (pintype "passive"))
      (node (ref "J3") (pin "1") (pinfunction "KL_1") (pintype "passive"))
      (node (ref "J4") (pin "1") (pinfunction "KL_1") (pintype "passive"))
      (node (ref "J5") (pin "1") (pinfunction "KL_1") (pintype "passive"))
      (node (ref "J6") (pin "1") (pinfunction "KL_1") (pintype "passive"))
      (node (ref "J7") (pin "1") (pinfunction "KL_1") (pintype "passive"))
      (node (ref "J8") (pin "1") (pinfunction "KL_1") (pintype "passive"))
      (node (ref "J9") (pin "4") (pinfunction "4_4") (pintype "passive"))
      (node (ref "JP13") (pin "1") (pinfunction "1_1") (pintype "passive"))
      (node (ref "JP15") (pin "2") (pinfunction "2_2") (pintype "passive"))
      (node (ref "JP16") (pin "1") (pinfunction "1_1") (pintype "passive"))
      (node (ref "JPAUX") (pin "2") (pinfunction "2_2") (pintype "passive"))
      (node (ref "R4") (pin "1") (pinfunction "1_1") (pintype "passive"))
      (node (ref "R7") (pin "1") (pinfunction "1_1") (pintype "passive"))
      (node (ref "REGUL3.3V") (pin "1") (pinfunction "GND_1") (pintype "power_in"))
      (node (ref "SW1") (pin "3") (pinfunction "3_3") (pintype "passive"))
      (node (ref "SW1") (pin "4") (pinfunction "4_4") (pintype "passive"))
      (node (ref "UCC") (pin "3") (pinfunction "GND_3") (pintype "bidirectional"))
      (node (ref "UCDA") (pin "3") (pinfunction "GND_3") (pintype "bidirectional"))
      (node (ref "UCDX") (pin "3") (pinfunction "GND_3") (pintype "bidirectional"))
      (node (ref "UCDY") (pin "3") (pinfunction "GND_3") (pintype "bidirectional"))
      (node (ref "UCDZ") (pin "3") (pinfunction "GND_3") (pintype "bidirectional"))
      (node (ref "UCEA") (pin "3") (pinfunction "GND_3") (pintype "bidirectional"))
      (node (ref "UCEY") (pin "3") (pinfunction "GND_3") (pintype "bidirectional"))
      (node (ref "UCEZ") (pin "3") (pinfunction "GND_3") (pintype "bidirectional"))
      (node (ref "UCS") (pin "3") (pinfunction "GND_3") (pintype "bidirectional"))
      (node (ref "UCSA") (pin "3") (pinfunction "GND_3") (pintype "bidirectional"))
      (node (ref "UCSD") (pin "3") (pinfunction "GND_3") (pintype "bidirectional"))
      (node (ref "UCSP") (pin "3") (pinfunction "GND_3") (pintype "bidirectional"))
      (node (ref "UCSX") (pin "3") (pinfunction "GND_3") (pintype "bidirectional"))
      (node (ref "UCSY") (pin "3") (pinfunction "GND_3") (pintype "bidirectional"))
      (node (ref "UCSZ") (pin "3") (pinfunction "GND_3") (pintype "bidirectional"))
      (node (ref "UNEX") (pin "3") (pinfunction "GND_3") (pintype "bidirectional"))
    )
    (net (code "65") (name "GND2") (class "Default")
      (node (ref "C1") (pin "-") (pinfunction "-_-") (pintype "passive"))
      (node (ref "C2") (pin "-") (pinfunction "-_-") (pintype "passive"))
      (node (ref "C3") (pin "1") (pinfunction "2_1") (pintype "passive"))
      (node (ref "D1") (pin "A") (pinfunction "A_A") (pintype "passive"))
      (node (ref "D13") (pin "3") (pinfunction "3_3") (pintype "passive"))
      (node (ref "IC2") (pin "3") (pinfunction "GND_3") (pintype "power_in"))
      (node (ref "IC2") (pin "5") (pinfunction "~{ON}/OFF_5") (pintype "input"))
      (node (ref "J1") (pin "1") (pinfunction "KL_1") (pintype "passive"))
      (node (ref "R4") (pin "2") (pinfunction "2_2") (pintype "passive"))
      (node (ref "R64") (pin "2") (pinfunction "2_2") (pintype "passive"))
    )
    (net (code "66") (name "Net-(16MHZ-1)") (class "Default")
      (node (ref "16MHZ") (pin "P$1") (pinfunction "1_P$1") (pintype "passive"))
      (node (ref "AVR_XMEGA192A3-AU") (pin "58") (pinfunction "PR0_58") (pintype "bidirectional"))
    )
    (net (code "67") (name "Net-(16MHZ-3)") (class "Default")
      (node (ref "16MHZ") (pin "P$2") (pinfunction "3_P$2") (pintype "passive"))
      (node (ref "AVR_XMEGA192A3-AU") (pin "59") (pinfunction "PR1_59") (pintype "bidirectional"))
    )
    (net (code "68") (name "Net-(C2-Pad+)") (class "Default")
      (node (ref "C2") (pin "+") (pinfunction "+_+") (pintype "passive"))
      (node (ref "JP1") (pin "2") (pinfunction "2_2") (pintype "passive"))
      (node (ref "L1") (pin "2") (pinfunction "2_2") (pintype "passive"))
      (node (ref "R65") (pin "A") (pinfunction "A_A") (pintype "passive"))
    )
    (net (code "69") (name "Net-(D2-PadA)") (class "Default")
      (node (ref "D2") (pin "A") (pinfunction "A_A") (pintype "passive"))
      (node (ref "R1") (pin "1") (pinfunction "1_1") (pintype "passive"))
    )
    (net (code "70") (name "Net-(D3-PadC)") (class "Default")
      (node (ref "D3") (pin "C") (pinfunction "C_C") (pintype "passive"))
      (node (ref "R2") (pin "1") (pinfunction "1_1") (pintype "passive"))
    )
    (net (code "71") (name "Net-(D4-PadC)") (class "Default")
      (node (ref "D4") (pin "C") (pinfunction "C_C") (pintype "passive"))
      (node (ref "R3") (pin "1") (pinfunction "1_1") (pintype "passive"))
    )
    (net (code "72") (name "Net-(D5-PadA)") (class "Default")
      (node (ref "D5") (pin "A") (pinfunction "A_A") (pintype "passive"))
      (node (ref "R18") (pin "1") (pinfunction "1_1") (pintype "passive"))
    )
    (net (code "73") (name "Net-(D6-PadA)") (class "Default")
      (node (ref "D6") (pin "A") (pinfunction "A_A") (pintype "passive"))
      (node (ref "R19") (pin "1") (pinfunction "1_1") (pintype "passive"))
    )
    (net (code "74") (name "Net-(D7-PadA)") (class "Default")
      (node (ref "D7") (pin "A") (pinfunction "A_A") (pintype "passive"))
      (node (ref "R20") (pin "1") (pinfunction "1_1") (pintype "passive"))
    )
    (net (code "75") (name "Net-(D8-PadA)") (class "Default")
      (node (ref "D8") (pin "A") (pinfunction "A_A") (pintype "passive"))
      (node (ref "R21") (pin "1") (pinfunction "1_1") (pintype "passive"))
    )
    (net (code "76") (name "Net-(D60-PadA)") (class "Default")
      (node (ref "D60") (pin "A") (pinfunction "A_A") (pintype "passive"))
      (node (ref "R60") (pin "1") (pinfunction "1_1") (pintype "passive"))
    )
    (net (code "77") (name "Net-(D61-PadA)") (class "Default")
      (node (ref "D61") (pin "A") (pinfunction "A_A") (pintype "passive"))
      (node (ref "R61") (pin "1") (pinfunction "1_1") (pintype "passive"))
    )
    (net (code "78") (name "Net-(D62-PadA)") (class "Default")
      (node (ref "D62") (pin "A") (pinfunction "A_A") (pintype "passive"))
      (node (ref "R62") (pin "1") (pinfunction "1_1") (pintype "passive"))
    )
    (net (code "79") (name "Net-(D63-PadA)") (class "Default")
      (node (ref "D63") (pin "A") (pinfunction "A_A") (pintype "passive"))
      (node (ref "R63") (pin "1") (pinfunction "1_1") (pintype "passive"))
    )
    (net (code "80") (name "Net-(IC1-TXD)") (class "Default")
      (node (ref "IC1") (pin "1") (pinfunction "TXD_1") (pintype "output"))
      (node (ref "R9") (pin "2") (pinfunction "2_2") (pintype "passive"))
    )
    (net (code "81") (name "Net-(IC2-FB)") (class "Default")
      (node (ref "IC2") (pin "4") (pinfunction "FB_4") (pintype "input"))
      (node (ref "R64") (pin "1") (pinfunction "1_1") (pintype "passive"))
      (node (ref "R65") (pin "S") (pinfunction "S_S") (pintype "passive"))
    )
    (net (code "82") (name "Net-(IC2-OUT)") (class "Default")
      (node (ref "D1") (pin "C") (pinfunction "C_C") (pintype "passive"))
      (node (ref "IC2") (pin "2") (pinfunction "OUT_2") (pintype "output"))
      (node (ref "L1") (pin "1") (pinfunction "1_1") (pintype "passive"))
    )
    (net (code "83") (name "Net-(J14-Pad2)") (class "Default")
      (node (ref "J14") (pin "2") (pinfunction "2_2") (pintype "passive"))
      (node (ref "R8") (pin "1") (pinfunction "1_1") (pintype "passive"))
    )
    (net (code "84") (name "unconnected-(AVR_XMEGA192A3-AU-PA3-Pad1)") (class "Default")
      (node (ref "AVR_XMEGA192A3-AU") (pin "1") (pinfunction "PA3_1") (pintype "bidirectional"))
    )
    (net (code "85") (name "unconnected-(AVR_XMEGA192A3-AU-PA4-Pad2)") (class "Default")
      (node (ref "AVR_XMEGA192A3-AU") (pin "2") (pinfunction "PA4_2") (pintype "bidirectional"))
    )
    (net (code "86") (name "unconnected-(AVR_XMEGA192A3-AU-PB1-Pad7)") (class "Default")
      (node (ref "AVR_XMEGA192A3-AU") (pin "7") (pinfunction "PB1_7") (pintype "bidirectional"))
    )
    (net (code "87") (name "unconnected-(AVR_XMEGA192A3-AU-PB2-Pad8)") (class "Default")
      (node (ref "AVR_XMEGA192A3-AU") (pin "8") (pinfunction "PB2_8") (pintype "bidirectional"))
    )
    (net (code "88") (name "unconnected-(AVR_XMEGA192A3-AU-PD3-Pad29)") (class "Default")
      (node (ref "AVR_XMEGA192A3-AU") (pin "29") (pinfunction "PD3_29") (pintype "bidirectional"))
    )
    (net (code "89") (name "unconnected-(AVR_XMEGA192A3-AU-PD4-Pad30)") (class "Default")
      (node (ref "AVR_XMEGA192A3-AU") (pin "30") (pinfunction "PD4_30") (pintype "bidirectional"))
    )
    (net (code "90") (name "unconnected-(AVR_XMEGA192A3-AU-PE3-Pad39)") (class "Default")
      (node (ref "AVR_XMEGA192A3-AU") (pin "39") (pinfunction "PE3_39") (pintype "bidirectional"))
    )
    (net (code "91") (name "unconnected-(AVR_XMEGA192A3-AU-PE4-Pad40)") (class "Default")
      (node (ref "AVR_XMEGA192A3-AU") (pin "40") (pinfunction "PE4_40") (pintype "bidirectional"))
    )
    (net (code "92") (name "unconnected-(AVR_XMEGA192A3-AU-PF3-Pad49)") (class "Default")
      (node (ref "AVR_XMEGA192A3-AU") (pin "49") (pinfunction "PF3_49") (pintype "bidirectional"))
    )
    (net (code "93") (name "unconnected-(AVR_XMEGA192A3-AU-PF4-Pad50)") (class "Default")
      (node (ref "AVR_XMEGA192A3-AU") (pin "50") (pinfunction "PF4_50") (pintype "bidirectional"))
    )
    (net (code "94") (name "unconnected-(IC1-CBUS0-Pad15)") (class "Default")
      (node (ref "IC1") (pin "15") (pinfunction "CBUS0_15") (pintype "bidirectional"))
    )
    (net (code "95") (name "unconnected-(IC1-CBUS3-Pad16)") (class "Default")
      (node (ref "IC1") (pin "16") (pinfunction "CBUS3_16") (pintype "bidirectional"))
    )
    (net (code "96") (name "unconnected-(J9-Pad1)") (class "Default")
      (node (ref "J9") (pin "1") (pinfunction "1_1") (pintype "passive"))
    )
    (net (code "97") (name "unconnected-(J10-Pad3)") (class "Default")
      (node (ref "J10") (pin "3") (pinfunction "3_3") (pintype "passive"))
    )
    (net (code "98") (name "unconnected-(J10-Pad4)") (class "Default")
      (node (ref "J10") (pin "4") (pinfunction "4_4") (pintype "passive"))
    )
    (net (code "99") (name "unconnected-(R65-PadE)") (class "Default")
      (node (ref "R65") (pin "E") (pinfunction "E_E") (pintype "passive"))
    )
    (net (code "100") (name "unconnected-(UCC-NC-Pad1)") (class "Default")
      (node (ref "UCC") (pin "1") (pinfunction "NC_1") (pintype "bidirectional"))
    )
    (net (code "101") (name "unconnected-(UCDA-NC-Pad1)") (class "Default")
      (node (ref "UCDA") (pin "1") (pinfunction "NC_1") (pintype "bidirectional"))
    )
    (net (code "102") (name "unconnected-(UCDX-NC-Pad1)") (class "Default")
      (node (ref "UCDX") (pin "1") (pinfunction "NC_1") (pintype "bidirectional"))
    )
    (net (code "103") (name "unconnected-(UCDY-NC-Pad1)") (class "Default")
      (node (ref "UCDY") (pin "1") (pinfunction "NC_1") (pintype "bidirectional"))
    )
    (net (code "104") (name "unconnected-(UCDZ-NC-Pad1)") (class "Default")
      (node (ref "UCDZ") (pin "1") (pinfunction "NC_1") (pintype "bidirectional"))
    )
    (net (code "105") (name "unconnected-(UCEA-NC-Pad1)") (class "Default")
      (node (ref "UCEA") (pin "1") (pinfunction "NC_1") (pintype "bidirectional"))
    )
    (net (code "106") (name "unconnected-(UCEY-NC-Pad1)") (class "Default")
      (node (ref "UCEY") (pin "1") (pinfunction "NC_1") (pintype "bidirectional"))
    )
    (net (code "107") (name "unconnected-(UCEZ-NC-Pad1)") (class "Default")
      (node (ref "UCEZ") (pin "1") (pinfunction "NC_1") (pintype "bidirectional"))
    )
    (net (code "108") (name "unconnected-(UCS-NC-Pad1)") (class "Default")
      (node (ref "UCS") (pin "1") (pinfunction "NC_1") (pintype "bidirectional"))
    )
    (net (code "109") (name "unconnected-(UCSA-NC-Pad1)") (class "Default")
      (node (ref "UCSA") (pin "1") (pinfunction "NC_1") (pintype "bidirectional"))
    )
    (net (code "110") (name "unconnected-(UCSD-NC-Pad1)") (class "Default")
      (node (ref "UCSD") (pin "1") (pinfunction "NC_1") (pintype "bidirectional"))
    )
    (net (code "111") (name "unconnected-(UCSP-NC-Pad1)") (class "Default")
      (node (ref "UCSP") (pin "1") (pinfunction "NC_1") (pintype "bidirectional"))
    )
    (net (code "112") (name "unconnected-(UCSX-NC-Pad1)") (class "Default")
      (node (ref "UCSX") (pin "1") (pinfunction "NC_1") (pintype "bidirectional"))
    )
    (net (code "113") (name "unconnected-(UCSY-NC-Pad1)") (class "Default")
      (node (ref "UCSY") (pin "1") (pinfunction "NC_1") (pintype "bidirectional"))
    )
    (net (code "114") (name "unconnected-(UCSZ-NC-Pad1)") (class "Default")
      (node (ref "UCSZ") (pin "1") (pinfunction "NC_1") (pintype "bidirectional"))
    )
    (net (code "115") (name "unconnected-(UNEX-NC-Pad1)") (class "Default")
      (node (ref "UNEX") (pin "1") (pinfunction "NC_1") (pintype "bidirectional"))
    )
  )
)
